# KIT_STM32F4.net
KiCad netlist of a schematic drawn in Altium Designer
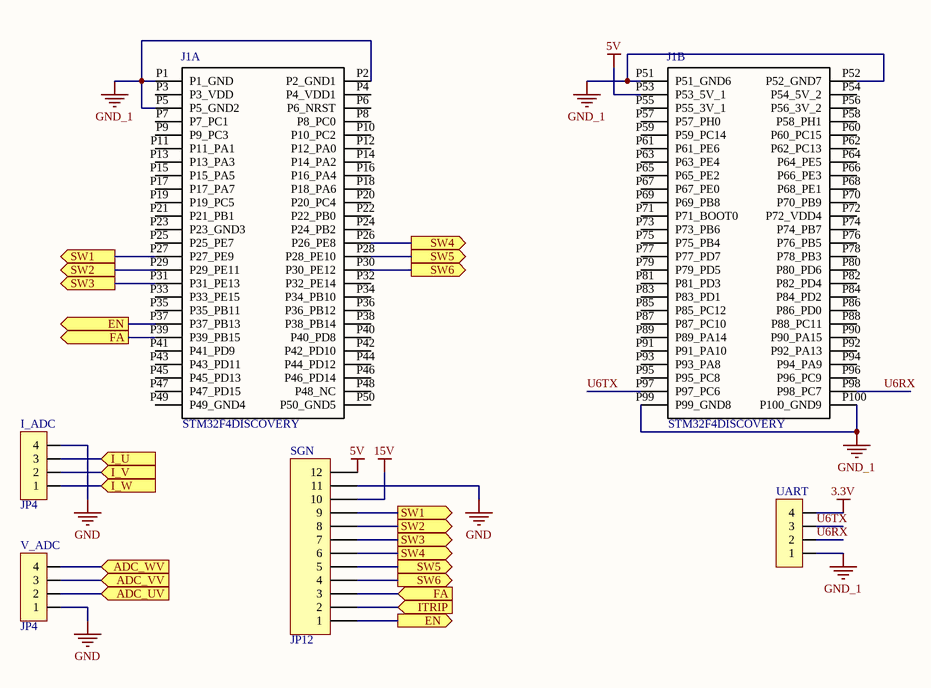
[diagram p0: KIT_STM32F4.SchDoc]

(export (version "E")
  (design (tool "Eeschema 10.0.6"))
  (components
    (comp (ref "I_ADC")
      (value "JP4")
      (footprint "JP4-C1T")
      (description "WR-PHD 2.54 mm Angled Socket Header")
      (fields
        (field (name "MANUFACTURER") "Würth Elektronik eiSos GmbH")
        (field (name "PARTNO") "613004143121")
        (field (name "CREATED BY") "Karrer Zheng")
      )
      (libsource (lib "LIBRARY") (part "JP4"))
    )
    (comp (ref "J1")
      (value "STM32F4DISCOVERY")
      (footprint "STMICROELECTRONICS_STM32F4DISCOVERY_STM32F4DISCOVERY(Primary)")
      (description "Development kit: ARM ST; pin strips, pin header; No.of")
      (fields (field (name "MF") "STMicroelectronics"))
      (libsource (lib "SemacSYS") (part "STM32F4DISCOVERY"))
    )
    (comp (ref "SGN")
      (value "JP12")
      (footprint "JP12-D1T")
      (description "WR-PHD 2.54 mm Angled Socket Header")
      (fields
        (field (name "MANUFACTURER") "Würth Elektronik eiSos GmbH")
        (field (name "PARTNO") "613012143121")
        (field (name "CREATED BY") "Karrer Zheng")
      )
      (libsource (lib "LIBRARY") (part "JP12"))
    )
    (comp (ref "UART")
      (value "JP4")
      (footprint "JP4-C1T")
      (description "WR-PHD 2.54 mm Angled Socket Header")
      (fields
        (field (name "MANUFACTURER") "Würth Elektronik eiSos GmbH")
        (field (name "PARTNO") "613004143121")
        (field (name "CREATED BY") "Karrer Zheng")
      )
      (libsource (lib "LIBRARY") (part "JP4"))
    )
    (comp (ref "V_ADC")
      (value "JP4")
      (footprint "JP4-C1T")
      (description "WR-PHD 2.54 mm Angled Socket Header")
      (fields
        (field (name "MANUFACTURER") "Würth Elektronik eiSos GmbH")
        (field (name "PARTNO") "613004143121")
        (field (name "CREATED BY") "Karrer Zheng")
      )
      (libsource (lib "LIBRARY") (part "JP4"))
    )
  )
  (nets
    (net (code "1") (name "/ADC_UV") (class "Default")
      (node (ref "V_ADC") (pin "2") (pinfunction "2_2") (pintype "passive"))
    )
    (net (code "2") (name "/ADC_VV") (class "Default")
      (node (ref "V_ADC") (pin "3") (pinfunction "3_3") (pintype "passive"))
    )
    (net (code "3") (name "/ADC_WV") (class "Default")
      (node (ref "V_ADC") (pin "4") (pinfunction "4_4") (pintype "passive"))
    )
    (net (code "4") (name "/EN") (class "Default")
      (node (ref "J1") (pin "P37") (pinfunction "P37_PB13_P37") (pintype "passive"))
      (node (ref "SGN") (pin "1") (pinfunction "1_1") (pintype "passive"))
    )
    (net (code "5") (name "/FA") (class "Default")
      (node (ref "J1") (pin "P39") (pinfunction "P39_PB15_P39") (pintype "passive"))
      (node (ref "SGN") (pin "3") (pinfunction "3_3") (pintype "passive"))
    )
    (net (code "6") (name "/ITRIP") (class "Default")
      (node (ref "SGN") (pin "2") (pinfunction "2_2") (pintype "passive"))
    )
    (net (code "7") (name "/I_U") (class "Default")
      (node (ref "I_ADC") (pin "3") (pinfunction "3_3") (pintype "passive"))
    )
    (net (code "8") (name "/I_V") (class "Default")
      (node (ref "I_ADC") (pin "2") (pinfunction "2_2") (pintype "passive"))
    )
    (net (code "9") (name "/I_W") (class "Default")
      (node (ref "I_ADC") (pin "1") (pinfunction "1_1") (pintype "passive"))
    )
    (net (code "10") (name "/SW1") (class "Default")
      (node (ref "J1") (pin "P27") (pinfunction "P27_PE9_P27") (pintype "passive"))
      (node (ref "SGN") (pin "9") (pinfunction "9_9") (pintype "passive"))
    )
    (net (code "11") (name "/SW2") (class "Default")
      (node (ref "J1") (pin "P29") (pinfunction "P29_PE11_P29") (pintype "passive"))
      (node (ref "SGN") (pin "8") (pinfunction "8_8") (pintype "passive"))
    )
    (net (code "12") (name "/SW3") (class "Default")
      (node (ref "J1") (pin "P31") (pinfunction "P31_PE13_P31") (pintype "passive"))
      (node (ref "SGN") (pin "7") (pinfunction "7_7") (pintype "passive"))
    )
    (net (code "13") (name "/SW4") (class "Default")
      (node (ref "J1") (pin "P26") (pinfunction "P26_PE8_P26") (pintype "passive"))
      (node (ref "SGN") (pin "6") (pinfunction "6_6") (pintype "passive"))
    )
    (net (code "14") (name "/SW5") (class "Default")
      (node (ref "J1") (pin "P28") (pinfunction "P28_PE10_P28") (pintype "passive"))
      (node (ref "SGN") (pin "5") (pinfunction "5_5") (pintype "passive"))
    )
    (net (code "15") (name "/SW6") (class "Default")
      (node (ref "J1") (pin "P30") (pinfunction "P30_PE12_P30") (pintype "passive"))
      (node (ref "SGN") (pin "4") (pinfunction "4_4") (pintype "passive"))
    )
    (net (code "16") (name "/U6RX") (class "Default")
      (node (ref "J1") (pin "P98") (pinfunction "P98_PC7_P98") (pintype "passive"))
      (node (ref "UART") (pin "2") (pinfunction "2_2") (pintype "passive"))
    )
    (net (code "17") (name "/U6TX") (class "Default")
      (node (ref "J1") (pin "P97") (pinfunction "P97_PC6_P97") (pintype "passive"))
      (node (ref "UART") (pin "3") (pinfunction "3_3") (pintype "passive"))
    )
    (net (code "18") (name "3.3V") (class "Default")
      (node (ref "UART") (pin "4") (pinfunction "4_4") (pintype "passive"))
    )
    (net (code "19") (name "5V") (class "Default")
      (node (ref "J1") (pin "P53") (pinfunction "P53_5V_1_P53") (pintype "passive"))
      (node (ref "SGN") (pin "12") (pinfunction "12_12") (pintype "passive"))
    )
    (net (code "20") (name "15V") (class "Default")
      (node (ref "SGN") (pin "10") (pinfunction "10_10") (pintype "passive"))
    )
    (net (code "21") (name "GND") (class "Default")
      (node (ref "I_ADC") (pin "4") (pinfunction "4_4") (pintype "passive"))
      (node (ref "SGN") (pin "11") (pinfunction "11_11") (pintype "passive"))
      (node (ref "V_ADC") (pin "1") (pinfunction "1_1") (pintype "passive"))
    )
    (net (code "22") (name "GND_1") (class "Default")
      (node (ref "J1") (pin "P1") (pinfunction "P1_GND_P1") (pintype "passive"))
      (node (ref "J1") (pin "P100") (pinfunction "P100_GND9_P100") (pintype "passive"))
      (node (ref "J1") (pin "P2") (pinfunction "P2_GND1_P2") (pintype "passive"))
      (node (ref "J1") (pin "P5") (pinfunction "P5_GND2_P5") (pintype "passive"))
      (node (ref "J1") (pin "P51") (pinfunction "P51_GND6_P51") (pintype "passive"))
      (node (ref "J1") (pin "P52") (pinfunction "P52_GND7_P52") (pintype "passive"))
      (node (ref "J1") (pin "P99") (pinfunction "P99_GND8_P99") (pintype "passive"))
      (node (ref "UART") (pin "1") (pinfunction "1_1") (pintype "passive"))
    )
    (net (code "23") (name "unconnected-(J1A-P3_VDD-PadP3)") (class "Default")
      (node (ref "J1") (pin "P3") (pinfunction "P3_VDD_P3") (pintype "passive"))
    )
    (net (code "24") (name "unconnected-(J1A-P4_VDD1-PadP4)") (class "Default")
      (node (ref "J1") (pin "P4") (pinfunction "P4_VDD1_P4") (pintype "passive"))
    )
    (net (code "25") (name "unconnected-(J1A-P6_NRST-PadP6)") (class "Default")
      (node (ref "J1") (pin "P6") (pinfunction "P6_NRST_P6") (pintype "passive"))
    )
    (net (code "26") (name "unconnected-(J1A-P7_PC1-PadP7)") (class "Default")
      (node (ref "J1") (pin "P7") (pinfunction "P7_PC1_P7") (pintype "passive"))
    )
    (net (code "27") (name "unconnected-(J1A-P8_PC0-PadP8)") (class "Default")
      (node (ref "J1") (pin "P8") (pinfunction "P8_PC0_P8") (pintype "passive"))
    )
    (net (code "28") (name "unconnected-(J1A-P9_PC3-PadP9)") (class "Default")
      (node (ref "J1") (pin "P9") (pinfunction "P9_PC3_P9") (pintype "passive"))
    )
    (net (code "29") (name "unconnected-(J1A-P10_PC2-PadP10)") (class "Default")
      (node (ref "J1") (pin "P10") (pinfunction "P10_PC2_P10") (pintype "passive"))
    )
    (net (code "30") (name "unconnected-(J1A-P11_PA1-PadP11)") (class "Default")
      (node (ref "J1") (pin "P11") (pinfunction "P11_PA1_P11") (pintype "passive"))
    )
    (net (code "31") (name "unconnected-(J1A-P12_PA0-PadP12)") (class "Default")
      (node (ref "J1") (pin "P12") (pinfunction "P12_PA0_P12") (pintype "passive"))
    )
    (net (code "32") (name "unconnected-(J1A-P13_PA3-PadP13)") (class "Default")
      (node (ref "J1") (pin "P13") (pinfunction "P13_PA3_P13") (pintype "passive"))
    )
    (net (code "33") (name "unconnected-(J1A-P14_PA2-PadP14)") (class "Default")
      (node (ref "J1") (pin "P14") (pinfunction "P14_PA2_P14") (pintype "passive"))
    )
    (net (code "34") (name "unconnected-(J1A-P15_PA5-PadP15)") (class "Default")
      (node (ref "J1") (pin "P15") (pinfunction "P15_PA5_P15") (pintype "passive"))
    )
    (net (code "35") (name "unconnected-(J1A-P16_PA4-PadP16)") (class "Default")
      (node (ref "J1") (pin "P16") (pinfunction "P16_PA4_P16") (pintype "passive"))
    )
    (net (code "36") (name "unconnected-(J1A-P17_PA7-PadP17)") (class "Default")
      (node (ref "J1") (pin "P17") (pinfunction "P17_PA7_P17") (pintype "passive"))
    )
    (net (code "37") (name "unconnected-(J1A-P18_PA6-PadP18)") (class "Default")
      (node (ref "J1") (pin "P18") (pinfunction "P18_PA6_P18") (pintype "passive"))
    )
    (net (code "38") (name "unconnected-(J1A-P19_PC5-PadP19)") (class "Default")
      (node (ref "J1") (pin "P19") (pinfunction "P19_PC5_P19") (pintype "passive"))
    )
    (net (code "39") (name "unconnected-(J1A-P20_PC4-PadP20)") (class "Default")
      (node (ref "J1") (pin "P20") (pinfunction "P20_PC4_P20") (pintype "passive"))
    )
    (net (code "40") (name "unconnected-(J1A-P21_PB1-PadP21)") (class "Default")
      (node (ref "J1") (pin "P21") (pinfunction "P21_PB1_P21") (pintype "passive"))
    )
    (net (code "41") (name "unconnected-(J1A-P22_PB0-PadP22)") (class "Default")
      (node (ref "J1") (pin "P22") (pinfunction "P22_PB0_P22") (pintype "passive"))
    )
    (net (code "42") (name "unconnected-(J1A-P23_GND3-PadP23)") (class "Default")
      (node (ref "J1") (pin "P23") (pinfunction "P23_GND3_P23") (pintype "passive"))
    )
    (net (code "43") (name "unconnected-(J1A-P24_PB2-PadP24)") (class "Default")
      (node (ref "J1") (pin "P24") (pinfunction "P24_PB2_P24") (pintype "passive"))
    )
    (net (code "44") (name "unconnected-(J1A-P25_PE7-PadP25)") (class "Default")
      (node (ref "J1") (pin "P25") (pinfunction "P25_PE7_P25") (pintype "passive"))
    )
    (net (code "45") (name "unconnected-(J1A-P32_PE14-PadP32)") (class "Default")
      (node (ref "J1") (pin "P32") (pinfunction "P32_PE14_P32") (pintype "passive"))
    )
    (net (code "46") (name "unconnected-(J1A-P33_PE15-PadP33)") (class "Default")
      (node (ref "J1") (pin "P33") (pinfunction "P33_PE15_P33") (pintype "passive"))
    )
    (net (code "47") (name "unconnected-(J1A-P34_PB10-PadP34)") (class "Default")
      (node (ref "J1") (pin "P34") (pinfunction "P34_PB10_P34") (pintype "passive"))
    )
    (net (code "48") (name "unconnected-(J1A-P35_PB11-PadP35)") (class "Default")
      (node (ref "J1") (pin "P35") (pinfunction "P35_PB11_P35") (pintype "passive"))
    )
    (net (code "49") (name "unconnected-(J1A-P36_PB12-PadP36)") (class "Default")
      (node (ref "J1") (pin "P36") (pinfunction "P36_PB12_P36") (pintype "passive"))
    )
    (net (code "50") (name "unconnected-(J1A-P38_PB14-PadP38)") (class "Default")
      (node (ref "J1") (pin "P38") (pinfunction "P38_PB14_P38") (pintype "passive"))
    )
    (net (code "51") (name "unconnected-(J1A-P40_PD8-PadP40)") (class "Default")
      (node (ref "J1") (pin "P40") (pinfunction "P40_PD8_P40") (pintype "passive"))
    )
    (net (code "52") (name "unconnected-(J1A-P41_PD9-PadP41)") (class "Default")
      (node (ref "J1") (pin "P41") (pinfunction "P41_PD9_P41") (pintype "passive"))
    )
    (net (code "53") (name "unconnected-(J1A-P42_PD10-PadP42)") (class "Default")
      (node (ref "J1") (pin "P42") (pinfunction "P42_PD10_P42") (pintype "passive"))
    )
    (net (code "54") (name "unconnected-(J1A-P43_PD11-PadP43)") (class "Default")
      (node (ref "J1") (pin "P43") (pinfunction "P43_PD11_P43") (pintype "passive"))
    )
    (net (code "55") (name "unconnected-(J1A-P44_PD12-PadP44)") (class "Default")
      (node (ref "J1") (pin "P44") (pinfunction "P44_PD12_P44") (pintype "passive"))
    )
    (net (code "56") (name "unconnected-(J1A-P45_PD13-PadP45)") (class "Default")
      (node (ref "J1") (pin "P45") (pinfunction "P45_PD13_P45") (pintype "passive"))
    )
    (net (code "57") (name "unconnected-(J1A-P46_PD14-PadP46)") (class "Default")
      (node (ref "J1") (pin "P46") (pinfunction "P46_PD14_P46") (pintype "passive"))
    )
    (net (code "58") (name "unconnected-(J1A-P47_PD15-PadP47)") (class "Default")
      (node (ref "J1") (pin "P47") (pinfunction "P47_PD15_P47") (pintype "passive"))
    )
    (net (code "59") (name "unconnected-(J1A-P48_NC-PadP48)") (class "Default")
      (node (ref "J1") (pin "P48") (pinfunction "P48_NC_P48") (pintype "passive"))
    )
    (net (code "60") (name "unconnected-(J1A-P49_GND4-PadP49)") (class "Default")
      (node (ref "J1") (pin "P49") (pinfunction "P49_GND4_P49") (pintype "passive"))
    )
    (net (code "61") (name "unconnected-(J1A-P50_GND5-PadP50)") (class "Default")
      (node (ref "J1") (pin "P50") (pinfunction "P50_GND5_P50") (pintype "passive"))
    )
    (net (code "62") (name "unconnected-(J1B-P54_5V_2-PadP54)") (class "Default")
      (node (ref "J1") (pin "P54") (pinfunction "P54_5V_2_P54") (pintype "passive"))
    )
    (net (code "63") (name "unconnected-(J1B-P55_3V_1-PadP55)") (class "Default")
      (node (ref "J1") (pin "P55") (pinfunction "P55_3V_1_P55") (pintype "passive"))
    )
    (net (code "64") (name "unconnected-(J1B-P56_3V_2-PadP56)") (class "Default")
      (node (ref "J1") (pin "P56") (pinfunction "P56_3V_2_P56") (pintype "passive"))
    )
    (net (code "65") (name "unconnected-(J1B-P57_PH0-PadP57)") (class "Default")
      (node (ref "J1") (pin "P57") (pinfunction "P57_PH0_P57") (pintype "passive"))
    )
    (net (code "66") (name "unconnected-(J1B-P58_PH1-PadP58)") (class "Default")
      (node (ref "J1") (pin "P58") (pinfunction "P58_PH1_P58") (pintype "passive"))
    )
    (net (code "67") (name "unconnected-(J1B-P59_PC14-PadP59)") (class "Default")
      (node (ref "J1") (pin "P59") (pinfunction "P59_PC14_P59") (pintype "passive"))
    )
    (net (code "68") (name "unconnected-(J1B-P60_PC15-PadP60)") (class "Default")
      (node (ref "J1") (pin "P60") (pinfunction "P60_PC15_P60") (pintype "passive"))
    )
    (net (code "69") (name "unconnected-(J1B-P61_PE6-PadP61)") (class "Default")
      (node (ref "J1") (pin "P61") (pinfunction "P61_PE6_P61") (pintype "passive"))
    )
    (net (code "70") (name "unconnected-(J1B-P62_PC13-PadP62)") (class "Default")
      (node (ref "J1") (pin "P62") (pinfunction "P62_PC13_P62") (pintype "passive"))
    )
    (net (code "71") (name "unconnected-(J1B-P63_PE4-PadP63)") (class "Default")
      (node (ref "J1") (pin "P63") (pinfunction "P63_PE4_P63") (pintype "passive"))
    )
    (net (code "72") (name "unconnected-(J1B-P64_PE5-PadP64)") (class "Default")
      (node (ref "J1") (pin "P64") (pinfunction "P64_PE5_P64") (pintype "passive"))
    )
    (net (code "73") (name "unconnected-(J1B-P65_PE2-PadP65)") (class "Default")
      (node (ref "J1") (pin "P65") (pinfunction "P65_PE2_P65") (pintype "passive"))
    )
    (net (code "74") (name "unconnected-(J1B-P66_PE3-PadP66)") (class "Default")
      (node (ref "J1") (pin "P66") (pinfunction "P66_PE3_P66") (pintype "passive"))
    )
    (net (code "75") (name "unconnected-(J1B-P67_PE0-PadP67)") (class "Default")
      (node (ref "J1") (pin "P67") (pinfunction "P67_PE0_P67") (pintype "passive"))
    )
    (net (code "76") (name "unconnected-(J1B-P68_PE1-PadP68)") (class "Default")
      (node (ref "J1") (pin "P68") (pinfunction "P68_PE1_P68") (pintype "passive"))
    )
    (net (code "77") (name "unconnected-(J1B-P69_PB8-PadP69)") (class "Default")
      (node (ref "J1") (pin "P69") (pinfunction "P69_PB8_P69") (pintype "passive"))
    )
    (net (code "78") (name "unconnected-(J1B-P70_PB9-PadP70)") (class "Default")
      (node (ref "J1") (pin "P70") (pinfunction "P70_PB9_P70") (pintype "passive"))
    )
    (net (code "79") (name "unconnected-(J1B-P71_BOOT0-PadP71)") (class "Default")
      (node (ref "J1") (pin "P71") (pinfunction "P71_BOOT0_P71") (pintype "passive"))
    )
    (net (code "80") (name "unconnected-(J1B-P72_VDD4-PadP72)") (class "Default")
      (node (ref "J1") (pin "P72") (pinfunction "P72_VDD4_P72") (pintype "passive"))
    )
    (net (code "81") (name "unconnected-(J1B-P73_PB6-PadP73)") (class "Default")
      (node (ref "J1") (pin "P73") (pinfunction "P73_PB6_P73") (pintype "passive"))
    )
    (net (code "82") (name "unconnected-(J1B-P74_PB7-PadP74)") (class "Default")
      (node (ref "J1") (pin "P74") (pinfunction "P74_PB7_P74") (pintype "passive"))
    )
    (net (code "83") (name "unconnected-(J1B-P75_PB4-PadP75)") (class "Default")
      (node (ref "J1") (pin "P75") (pinfunction "P75_PB4_P75") (pintype "passive"))
    )
    (net (code "84") (name "unconnected-(J1B-P76_PB5-PadP76)") (class "Default")
      (node (ref "J1") (pin "P76") (pinfunction "P76_PB5_P76") (pintype "passive"))
    )
    (net (code "85") (name "unconnected-(J1B-P77_PD7-PadP77)") (class "Default")
      (node (ref "J1") (pin "P77") (pinfunction "P77_PD7_P77") (pintype "passive"))
    )
    (net (code "86") (name "unconnected-(J1B-P78_PB3-PadP78)") (class "Default")
      (node (ref "J1") (pin "P78") (pinfunction "P78_PB3_P78") (pintype "passive"))
    )
    (net (code "87") (name "unconnected-(J1B-P79_PD5-PadP79)") (class "Default")
      (node (ref "J1") (pin "P79") (pinfunction "P79_PD5_P79") (pintype "passive"))
    )
    (net (code "88") (name "unconnected-(J1B-P80_PD6-PadP80)") (class "Default")
      (node (ref "J1") (pin "P80") (pinfunction "P80_PD6_P80") (pintype "passive"))
    )
    (net (code "89") (name "unconnected-(J1B-P81_PD3-PadP81)") (class "Default")
      (node (ref "J1") (pin "P81") (pinfunction "P81_PD3_P81") (pintype "passive"))
    )
    (net (code "90") (name "unconnected-(J1B-P82_PD4-PadP82)") (class "Default")
      (node (ref "J1") (pin "P82") (pinfunction "P82_PD4_P82") (pintype "passive"))
    )
    (net (code "91") (name "unconnected-(J1B-P83_PD1-PadP83)") (class "Default")
      (node (ref "J1") (pin "P83") (pinfunction "P83_PD1_P83") (pintype "passive"))
    )
    (net (code "92") (name "unconnected-(J1B-P84_PD2-PadP84)") (class "Default")
      (node (ref "J1") (pin "P84") (pinfunction "P84_PD2_P84") (pintype "passive"))
    )
    (net (code "93") (name "unconnected-(J1B-P85_PC12-PadP85)") (class "Default")
      (node (ref "J1") (pin "P85") (pinfunction "P85_PC12_P85") (pintype "passive"))
    )
    (net (code "94") (name "unconnected-(J1B-P86_PD0-PadP86)") (class "Default")
      (node (ref "J1") (pin "P86") (pinfunction "P86_PD0_P86") (pintype "passive"))
    )
    (net (code "95") (name "unconnected-(J1B-P87_PC10-PadP87)") (class "Default")
      (node (ref "J1") (pin "P87") (pinfunction "P87_PC10_P87") (pintype "passive"))
    )
    (net (code "96") (name "unconnected-(J1B-P88_PC11-PadP88)") (class "Default")
      (node (ref "J1") (pin "P88") (pinfunction "P88_PC11_P88") (pintype "passive"))
    )
    (net (code "97") (name "unconnected-(J1B-P89_PA14-PadP89)") (class "Default")
      (node (ref "J1") (pin "P89") (pinfunction "P89_PA14_P89") (pintype "passive"))
    )
    (net (code "98") (name "unconnected-(J1B-P90_PA15-PadP90)") (class "Default")
      (node (ref "J1") (pin "P90") (pinfunction "P90_PA15_P90") (pintype "passive"))
    )
    (net (code "99") (name "unconnected-(J1B-P91_PA10-PadP91)") (class "Default")
      (node (ref "J1") (pin "P91") (pinfunction "P91_PA10_P91") (pintype "passive"))
    )
    (net (code "100") (name "unconnected-(J1B-P92_PA13-PadP92)") (class "Default")
      (node (ref "J1") (pin "P92") (pinfunction "P92_PA13_P92") (pintype "passive"))
    )
    (net (code "101") (name "unconnected-(J1B-P93_PA8-PadP93)") (class "Default")
      (node (ref "J1") (pin "P93") (pinfunction "P93_PA8_P93") (pintype "passive"))
    )
    (net (code "102") (name "unconnected-(J1B-P94_PA9-PadP94)") (class "Default")
      (node (ref "J1") (pin "P94") (pinfunction "P94_PA9_P94") (pintype "passive"))
    )
    (net (code "103") (name "unconnected-(J1B-P95_PC8-PadP95)") (class "Default")
      (node (ref "J1") (pin "P95") (pinfunction "P95_PC8_P95") (pintype "passive"))
    )
    (net (code "104") (name "unconnected-(J1B-P96_PC9-PadP96)") (class "Default")
      (node (ref "J1") (pin "P96") (pinfunction "P96_PC9_P96") (pintype "passive"))
    )
  )
)
